# Mosfets.net
KiCad netlist of a schematic drawn in EAGLE
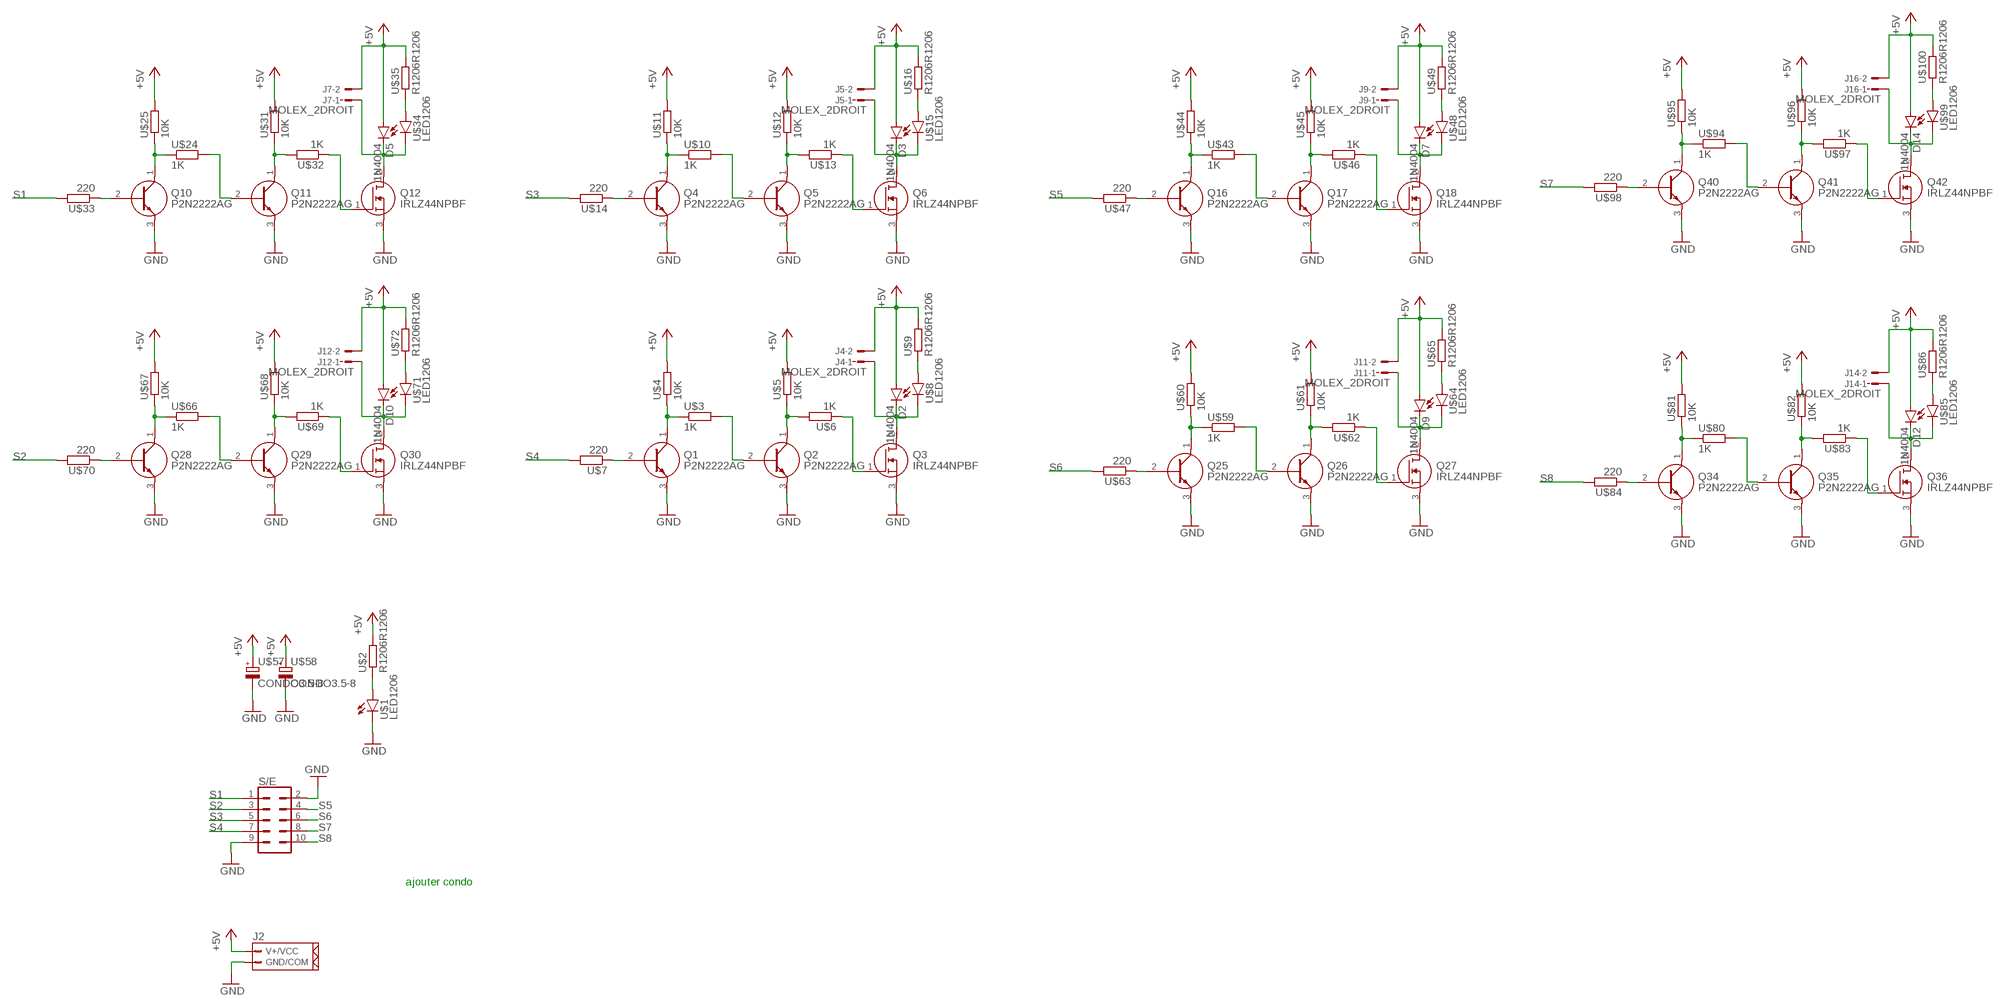
[diagram p0: schematic, sheet 1]

(export (version "E")
  (design (tool "Eeschema 10.0.6"))
  (components
    (comp (ref "D2")
      (value "1N4004")
      (footprint "eagle-import:DO41-10")
      (libsource (lib "eagle-import") (part "1N4004"))
    )
    (comp (ref "D3")
      (value "1N4004")
      (footprint "eagle-import:DO41-10")
      (libsource (lib "eagle-import") (part "1N4004"))
    )
    (comp (ref "D5")
      (value "1N4004")
      (footprint "eagle-import:DO41-10")
      (libsource (lib "eagle-import") (part "1N4004"))
    )
    (comp (ref "D7")
      (value "1N4004")
      (footprint "eagle-import:DO41-10")
      (libsource (lib "eagle-import") (part "1N4004"))
    )
    (comp (ref "D9")
      (value "1N4004")
      (footprint "eagle-import:DO41-10")
      (libsource (lib "eagle-import") (part "1N4004"))
    )
    (comp (ref "D10")
      (value "1N4004")
      (footprint "eagle-import:DO41-10")
      (libsource (lib "eagle-import") (part "1N4004"))
    )
    (comp (ref "D12")
      (value "1N4004")
      (footprint "eagle-import:DO41-10")
      (libsource (lib "eagle-import") (part "1N4004"))
    )
    (comp (ref "D14")
      (value "1N4004")
      (footprint "eagle-import:DO41-10")
      (libsource (lib "eagle-import") (part "1N4004"))
    )
    (comp (ref "J2")
      (value "MOLEX_2_PUISS90°")
      (footprint "eagle-import:CON_2_PUISS_90°")
      (libsource (lib "eagle-import") (part "MOLEX_2_PUISS90°"))
    )
    (comp (ref "J4")
      (value "MOLEX_2DROIT")
      (footprint "eagle-import:CON_2_DROIT")
      (fields (field (name "MF") "MOLEX"))
      (libsource (lib "eagle-import") (part "MOLEX_2DROIT"))
    )
    (comp (ref "J5")
      (value "MOLEX_2DROIT")
      (footprint "eagle-import:CON_2_DROIT")
      (fields (field (name "MF") "MOLEX"))
      (libsource (lib "eagle-import") (part "MOLEX_2DROIT"))
    )
    (comp (ref "J7")
      (value "MOLEX_2DROIT")
      (footprint "eagle-import:CON_2_DROIT")
      (fields (field (name "MF") "MOLEX"))
      (libsource (lib "eagle-import") (part "MOLEX_2DROIT"))
    )
    (comp (ref "J9")
      (value "MOLEX_2DROIT")
      (footprint "eagle-import:CON_2_DROIT")
      (fields (field (name "MF") "MOLEX"))
      (libsource (lib "eagle-import") (part "MOLEX_2DROIT"))
    )
    (comp (ref "J11")
      (value "MOLEX_2DROIT")
      (footprint "eagle-import:CON_2_DROIT")
      (fields (field (name "MF") "MOLEX"))
      (libsource (lib "eagle-import") (part "MOLEX_2DROIT"))
    )
    (comp (ref "J12")
      (value "MOLEX_2DROIT")
      (footprint "eagle-import:CON_2_DROIT")
      (fields (field (name "MF") "MOLEX"))
      (libsource (lib "eagle-import") (part "MOLEX_2DROIT"))
    )
    (comp (ref "J14")
      (value "MOLEX_2DROIT")
      (footprint "eagle-import:CON_2_DROIT")
      (fields (field (name "MF") "MOLEX"))
      (libsource (lib "eagle-import") (part "MOLEX_2DROIT"))
    )
    (comp (ref "J16")
      (value "MOLEX_2DROIT")
      (footprint "eagle-import:CON_2_DROIT")
      (fields (field (name "MF") "MOLEX"))
      (libsource (lib "eagle-import") (part "MOLEX_2DROIT"))
    )
    (comp (ref "Q1")
      (value "P2N2222AG")
      (footprint "eagle-import:TO-92")
      (fields (field (name "MOUSER_PART_NUMBER") "863-P2N2222AG") (field (name "RS_PART_NUMBER") "5449624P"))
      (libsource (lib "eagle-import") (part "P2N2222AG"))
    )
    (comp (ref "Q2")
      (value "P2N2222AG")
      (footprint "eagle-import:TO-92")
      (fields (field (name "MOUSER_PART_NUMBER") "863-P2N2222AG") (field (name "RS_PART_NUMBER") "5449624P"))
      (libsource (lib "eagle-import") (part "P2N2222AG"))
    )
    (comp (ref "Q3")
      (value "IRLZ44NPBF")
      (footprint "eagle-import:TO254P469X1042X1967-3P")
      (fields (field (name "RS_PART_NUMBER") "2509061408"))
      (libsource (lib "eagle-import") (part "IRLZ44NPBF"))
    )
    (comp (ref "Q4")
      (value "P2N2222AG")
      (footprint "eagle-import:TO-92")
      (fields (field (name "MOUSER_PART_NUMBER") "863-P2N2222AG") (field (name "RS_PART_NUMBER") "5449624P"))
      (libsource (lib "eagle-import") (part "P2N2222AG"))
    )
    (comp (ref "Q5")
      (value "P2N2222AG")
      (footprint "eagle-import:TO-92")
      (fields (field (name "MOUSER_PART_NUMBER") "863-P2N2222AG") (field (name "RS_PART_NUMBER") "5449624P"))
      (libsource (lib "eagle-import") (part "P2N2222AG"))
    )
    (comp (ref "Q6")
      (value "IRLZ44NPBF")
      (footprint "eagle-import:TO254P469X1042X1967-3P")
      (fields (field (name "RS_PART_NUMBER") "2509061408"))
      (libsource (lib "eagle-import") (part "IRLZ44NPBF"))
    )
    (comp (ref "Q10")
      (value "P2N2222AG")
      (footprint "eagle-import:TO-92")
      (fields (field (name "MOUSER_PART_NUMBER") "863-P2N2222AG") (field (name "RS_PART_NUMBER") "5449624P"))
      (libsource (lib "eagle-import") (part "P2N2222AG"))
    )
    (comp (ref "Q11")
      (value "P2N2222AG")
      (footprint "eagle-import:TO-92")
      (fields (field (name "MOUSER_PART_NUMBER") "863-P2N2222AG") (field (name "RS_PART_NUMBER") "5449624P"))
      (libsource (lib "eagle-import") (part "P2N2222AG"))
    )
    (comp (ref "Q12")
      (value "IRLZ44NPBF")
      (footprint "eagle-import:TO254P469X1042X1967-3P")
      (fields (field (name "RS_PART_NUMBER") "2509061408"))
      (libsource (lib "eagle-import") (part "IRLZ44NPBF"))
    )
    (comp (ref "Q16")
      (value "P2N2222AG")
      (footprint "eagle-import:TO-92")
      (fields (field (name "MOUSER_PART_NUMBER") "863-P2N2222AG") (field (name "RS_PART_NUMBER") "5449624P"))
      (libsource (lib "eagle-import") (part "P2N2222AG"))
    )
    (comp (ref "Q17")
      (value "P2N2222AG")
      (footprint "eagle-import:TO-92")
      (fields (field (name "MOUSER_PART_NUMBER") "863-P2N2222AG") (field (name "RS_PART_NUMBER") "5449624P"))
      (libsource (lib "eagle-import") (part "P2N2222AG"))
    )
    (comp (ref "Q18")
      (value "IRLZ44NPBF")
      (footprint "eagle-import:TO254P469X1042X1967-3P")
      (fields (field (name "RS_PART_NUMBER") "2509061408"))
      (libsource (lib "eagle-import") (part "IRLZ44NPBF"))
    )
    (comp (ref "Q25")
      (value "P2N2222AG")
      (footprint "eagle-import:TO-92")
      (fields (field (name "MOUSER_PART_NUMBER") "863-P2N2222AG") (field (name "RS_PART_NUMBER") "5449624P"))
      (libsource (lib "eagle-import") (part "P2N2222AG"))
    )
    (comp (ref "Q26")
      (value "P2N2222AG")
      (footprint "eagle-import:TO-92")
      (fields (field (name "MOUSER_PART_NUMBER") "863-P2N2222AG") (field (name "RS_PART_NUMBER") "5449624P"))
      (libsource (lib "eagle-import") (part "P2N2222AG"))
    )
    (comp (ref "Q27")
      (value "IRLZ44NPBF")
      (footprint "eagle-import:TO254P469X1042X1967-3P")
      (fields (field (name "RS_PART_NUMBER") "2509061408"))
      (libsource (lib "eagle-import") (part "IRLZ44NPBF"))
    )
    (comp (ref "Q28")
      (value "P2N2222AG")
      (footprint "eagle-import:TO-92")
      (fields (field (name "MOUSER_PART_NUMBER") "863-P2N2222AG") (field (name "RS_PART_NUMBER") "5449624P"))
      (libsource (lib "eagle-import") (part "P2N2222AG"))
    )
    (comp (ref "Q29")
      (value "P2N2222AG")
      (footprint "eagle-import:TO-92")
      (fields (field (name "MOUSER_PART_NUMBER") "863-P2N2222AG") (field (name "RS_PART_NUMBER") "5449624P"))
      (libsource (lib "eagle-import") (part "P2N2222AG"))
    )
    (comp (ref "Q30")
      (value "IRLZ44NPBF")
      (footprint "eagle-import:TO254P469X1042X1967-3P")
      (fields (field (name "RS_PART_NUMBER") "2509061408"))
      (libsource (lib "eagle-import") (part "IRLZ44NPBF"))
    )
    (comp (ref "Q34")
      (value "P2N2222AG")
      (footprint "eagle-import:TO-92")
      (fields (field (name "MOUSER_PART_NUMBER") "863-P2N2222AG") (field (name "RS_PART_NUMBER") "5449624P"))
      (libsource (lib "eagle-import") (part "P2N2222AG"))
    )
    (comp (ref "Q35")
      (value "P2N2222AG")
      (footprint "eagle-import:TO-92")
      (fields (field (name "MOUSER_PART_NUMBER") "863-P2N2222AG") (field (name "RS_PART_NUMBER") "5449624P"))
      (libsource (lib "eagle-import") (part "P2N2222AG"))
    )
    (comp (ref "Q36")
      (value "IRLZ44NPBF")
      (footprint "eagle-import:TO254P469X1042X1967-3P")
      (fields (field (name "RS_PART_NUMBER") "2509061408"))
      (libsource (lib "eagle-import") (part "IRLZ44NPBF"))
    )
    (comp (ref "Q40")
      (value "P2N2222AG")
      (footprint "eagle-import:TO-92")
      (fields (field (name "MOUSER_PART_NUMBER") "863-P2N2222AG") (field (name "RS_PART_NUMBER") "5449624P"))
      (libsource (lib "eagle-import") (part "P2N2222AG"))
    )
    (comp (ref "Q41")
      (value "P2N2222AG")
      (footprint "eagle-import:TO-92")
      (fields (field (name "MOUSER_PART_NUMBER") "863-P2N2222AG") (field (name "RS_PART_NUMBER") "5449624P"))
      (libsource (lib "eagle-import") (part "P2N2222AG"))
    )
    (comp (ref "Q42")
      (value "IRLZ44NPBF")
      (footprint "eagle-import:TO254P469X1042X1967-3P")
      (fields (field (name "RS_PART_NUMBER") "2509061408"))
      (libsource (lib "eagle-import") (part "IRLZ44NPBF"))
    )
    (comp (ref "S/E")
      (value "CON_5X2SHD")
      (footprint "eagle-import:2X5-SHROUDED")
      (libsource (lib "eagle-import") (part "CON_5X2SHD"))
    )
    (comp (ref "U$1")
      (value "LED1206")
      (footprint "eagle-import:1206")
      (libsource (lib "eagle-import") (part "LED1206"))
    )
    (comp (ref "U$2")
      (value "R1206R1206")
      (footprint "eagle-import:R1206")
      (libsource (lib "eagle-import") (part "R1206R1206"))
    )
    (comp (ref "U$3")
      (value "1K")
      (footprint "eagle-import:R1206")
      (libsource (lib "eagle-import") (part "R1206R1206"))
    )
    (comp (ref "U$4")
      (value "10K")
      (footprint "eagle-import:R1206")
      (libsource (lib "eagle-import") (part "R1206R1206"))
    )
    (comp (ref "U$5")
      (value "10K")
      (footprint "eagle-import:R1206")
      (libsource (lib "eagle-import") (part "R1206R1206"))
    )
    (comp (ref "U$6")
      (value "1K")
      (footprint "eagle-import:R1206")
      (libsource (lib "eagle-import") (part "R1206R1206"))
    )
    (comp (ref "U$7")
      (value "220")
      (footprint "eagle-import:R1206")
      (libsource (lib "eagle-import") (part "R1206R1206"))
    )
    (comp (ref "U$8")
      (value "LED1206")
      (footprint "eagle-import:1206")
      (libsource (lib "eagle-import") (part "LED1206"))
    )
    (comp (ref "U$9")
      (value "R1206R1206")
      (footprint "eagle-import:R1206")
      (libsource (lib "eagle-import") (part "R1206R1206"))
    )
    (comp (ref "U$10")
      (value "1K")
      (footprint "eagle-import:R1206")
      (libsource (lib "eagle-import") (part "R1206R1206"))
    )
    (comp (ref "U$11")
      (value "10K")
      (footprint "eagle-import:R1206")
      (libsource (lib "eagle-import") (part "R1206R1206"))
    )
    (comp (ref "U$12")
      (value "10K")
      (footprint "eagle-import:R1206")
      (libsource (lib "eagle-import") (part "R1206R1206"))
    )
    (comp (ref "U$13")
      (value "1K")
      (footprint "eagle-import:R1206")
      (libsource (lib "eagle-import") (part "R1206R1206"))
    )
    (comp (ref "U$14")
      (value "220")
      (footprint "eagle-import:R1206")
      (libsource (lib "eagle-import") (part "R1206R1206"))
    )
    (comp (ref "U$15")
      (value "LED1206")
      (footprint "eagle-import:1206")
      (libsource (lib "eagle-import") (part "LED1206"))
    )
    (comp (ref "U$16")
      (value "R1206R1206")
      (footprint "eagle-import:R1206")
      (libsource (lib "eagle-import") (part "R1206R1206"))
    )
    (comp (ref "U$24")
      (value "1K")
      (footprint "eagle-import:R1206")
      (libsource (lib "eagle-import") (part "R1206R1206"))
    )
    (comp (ref "U$25")
      (value "10K")
      (footprint "eagle-import:R1206")
      (libsource (lib "eagle-import") (part "R1206R1206"))
    )
    (comp (ref "U$31")
      (value "10K")
      (footprint "eagle-import:R1206")
      (libsource (lib "eagle-import") (part "R1206R1206"))
    )
    (comp (ref "U$32")
      (value "1K")
      (footprint "eagle-import:R1206")
      (libsource (lib "eagle-import") (part "R1206R1206"))
    )
    (comp (ref "U$33")
      (value "220")
      (footprint "eagle-import:R1206")
      (libsource (lib "eagle-import") (part "R1206R1206"))
    )
    (comp (ref "U$34")
      (value "LED1206")
      (footprint "eagle-import:1206")
      (libsource (lib "eagle-import") (part "LED1206"))
    )
    (comp (ref "U$35")
      (value "R1206R1206")
      (footprint "eagle-import:R1206")
      (libsource (lib "eagle-import") (part "R1206R1206"))
    )
    (comp (ref "U$43")
      (value "1K")
      (footprint "eagle-import:R1206")
      (libsource (lib "eagle-import") (part "R1206R1206"))
    )
    (comp (ref "U$44")
      (value "10K")
      (footprint "eagle-import:R1206")
      (libsource (lib "eagle-import") (part "R1206R1206"))
    )
    (comp (ref "U$45")
      (value "10K")
      (footprint "eagle-import:R1206")
      (libsource (lib "eagle-import") (part "R1206R1206"))
    )
    (comp (ref "U$46")
      (value "1K")
      (footprint "eagle-import:R1206")
      (libsource (lib "eagle-import") (part "R1206R1206"))
    )
    (comp (ref "U$47")
      (value "220")
      (footprint "eagle-import:R1206")
      (libsource (lib "eagle-import") (part "R1206R1206"))
    )
    (comp (ref "U$48")
      (value "LED1206")
      (footprint "eagle-import:1206")
      (libsource (lib "eagle-import") (part "LED1206"))
    )
    (comp (ref "U$49")
      (value "R1206R1206")
      (footprint "eagle-import:R1206")
      (libsource (lib "eagle-import") (part "R1206R1206"))
    )
    (comp (ref "U$57")
      (value "CONDO3.5-8")
      (footprint "eagle-import:E3,5-8")
      (libsource (lib "eagle-import") (part "CONDO3.5-8"))
    )
    (comp (ref "U$58")
      (value "CONDO3.5-8")
      (footprint "eagle-import:E3,5-8")
      (libsource (lib "eagle-import") (part "CONDO3.5-8"))
    )
    (comp (ref "U$59")
      (value "1K")
      (footprint "eagle-import:R1206")
      (libsource (lib "eagle-import") (part "R1206R1206"))
    )
    (comp (ref "U$60")
      (value "10K")
      (footprint "eagle-import:R1206")
      (libsource (lib "eagle-import") (part "R1206R1206"))
    )
    (comp (ref "U$61")
      (value "10K")
      (footprint "eagle-import:R1206")
      (libsource (lib "eagle-import") (part "R1206R1206"))
    )
    (comp (ref "U$62")
      (value "1K")
      (footprint "eagle-import:R1206")
      (libsource (lib "eagle-import") (part "R1206R1206"))
    )
    (comp (ref "U$63")
      (value "220")
      (footprint "eagle-import:R1206")
      (libsource (lib "eagle-import") (part "R1206R1206"))
    )
    (comp (ref "U$64")
      (value "LED1206")
      (footprint "eagle-import:1206")
      (libsource (lib "eagle-import") (part "LED1206"))
    )
    (comp (ref "U$65")
      (value "R1206R1206")
      (footprint "eagle-import:R1206")
      (libsource (lib "eagle-import") (part "R1206R1206"))
    )
    (comp (ref "U$66")
      (value "1K")
      (footprint "eagle-import:R1206")
      (libsource (lib "eagle-import") (part "R1206R1206"))
    )
    (comp (ref "U$67")
      (value "10K")
      (footprint "eagle-import:R1206")
      (libsource (lib "eagle-import") (part "R1206R1206"))
    )
    (comp (ref "U$68")
      (value "10K")
      (footprint "eagle-import:R1206")
      (libsource (lib "eagle-import") (part "R1206R1206"))
    )
    (comp (ref "U$69")
      (value "1K")
      (footprint "eagle-import:R1206")
      (libsource (lib "eagle-import") (part "R1206R1206"))
    )
    (comp (ref "U$70")
      (value "220")
      (footprint "eagle-import:R1206")
      (libsource (lib "eagle-import") (part "R1206R1206"))
    )
    (comp (ref "U$71")
      (value "LED1206")
      (footprint "eagle-import:1206")
      (libsource (lib "eagle-import") (part "LED1206"))
    )
    (comp (ref "U$72")
      (value "R1206R1206")
      (footprint "eagle-import:R1206")
      (libsource (lib "eagle-import") (part "R1206R1206"))
    )
    (comp (ref "U$80")
      (value "1K")
      (footprint "eagle-import:R1206")
      (libsource (lib "eagle-import") (part "R1206R1206"))
    )
    (comp (ref "U$81")
      (value "10K")
      (footprint "eagle-import:R1206")
      (libsource (lib "eagle-import") (part "R1206R1206"))
    )
    (comp (ref "U$82")
      (value "10K")
      (footprint "eagle-import:R1206")
      (libsource (lib "eagle-import") (part "R1206R1206"))
    )
    (comp (ref "U$83")
      (value "1K")
      (footprint "eagle-import:R1206")
      (libsource (lib "eagle-import") (part "R1206R1206"))
    )
    (comp (ref "U$84")
      (value "220")
      (footprint "eagle-import:R1206")
      (libsource (lib "eagle-import") (part "R1206R1206"))
    )
    (comp (ref "U$85")
      (value "LED1206")
      (footprint "eagle-import:1206")
      (libsource (lib "eagle-import") (part "LED1206"))
    )
    (comp (ref "U$86")
      (value "R1206R1206")
      (footprint "eagle-import:R1206")
      (libsource (lib "eagle-import") (part "R1206R1206"))
    )
    (comp (ref "U$94")
      (value "1K")
      (footprint "eagle-import:R1206")
      (libsource (lib "eagle-import") (part "R1206R1206"))
    )
    (comp (ref "U$95")
      (value "10K")
      (footprint "eagle-import:R1206")
      (libsource (lib "eagle-import") (part "R1206R1206"))
    )
    (comp (ref "U$96")
      (value "10K")
      (footprint "eagle-import:R1206")
      (libsource (lib "eagle-import") (part "R1206R1206"))
    )
    (comp (ref "U$97")
      (value "1K")
      (footprint "eagle-import:R1206")
      (libsource (lib "eagle-import") (part "R1206R1206"))
    )
    (comp (ref "U$98")
      (value "220")
      (footprint "eagle-import:R1206")
      (libsource (lib "eagle-import") (part "R1206R1206"))
    )
    (comp (ref "U$99")
      (value "LED1206")
      (footprint "eagle-import:1206")
      (libsource (lib "eagle-import") (part "LED1206"))
    )
    (comp (ref "U$100")
      (value "R1206R1206")
      (footprint "eagle-import:R1206")
      (libsource (lib "eagle-import") (part "R1206R1206"))
    )
  )
  (nets
    (net (code "1") (name "+5V") (class "Default")
      (node (ref "D10") (pin "A") (pinfunction "A_A") (pintype "passive"))
      (node (ref "D12") (pin "A") (pinfunction "A_A") (pintype "passive"))
      (node (ref "D14") (pin "A") (pinfunction "A_A") (pintype "passive"))
      (node (ref "D2") (pin "A") (pinfunction "A_A") (pintype "passive"))
      (node (ref "D3") (pin "A") (pinfunction "A_A") (pintype "passive"))
      (node (ref "D5") (pin "A") (pinfunction "A_A") (pintype "passive"))
      (node (ref "D7") (pin "A") (pinfunction "A_A") (pintype "passive"))
      (node (ref "D9") (pin "A") (pinfunction "A_A") (pintype "passive"))
      (node (ref "J11") (pin "2") (pinfunction "S_2") (pintype "passive"))
      (node (ref "J12") (pin "2") (pinfunction "S_2") (pintype "passive"))
      (node (ref "J14") (pin "2") (pinfunction "S_2") (pintype "passive"))
      (node (ref "J16") (pin "2") (pinfunction "S_2") (pintype "passive"))
      (node (ref "J2") (pin "P$2") (pinfunction "V+/VCC_P$2") (pintype "passive"))
      (node (ref "J4") (pin "2") (pinfunction "S_2") (pintype "passive"))
      (node (ref "J5") (pin "2") (pinfunction "S_2") (pintype "passive"))
      (node (ref "J7") (pin "2") (pinfunction "S_2") (pintype "passive"))
      (node (ref "J9") (pin "2") (pinfunction "S_2") (pintype "passive"))
      (node (ref "U$100") (pin "2") (pinfunction "2_2") (pintype "passive"))
      (node (ref "U$11") (pin "2") (pinfunction "2_2") (pintype "passive"))
      (node (ref "U$12") (pin "2") (pinfunction "2_2") (pintype "passive"))
      (node (ref "U$16") (pin "2") (pinfunction "2_2") (pintype "passive"))
      (node (ref "U$2") (pin "2") (pinfunction "2_2") (pintype "passive"))
      (node (ref "U$25") (pin "2") (pinfunction "2_2") (pintype "passive"))
      (node (ref "U$31") (pin "2") (pinfunction "2_2") (pintype "passive"))
      (node (ref "U$35") (pin "2") (pinfunction "2_2") (pintype "passive"))
      (node (ref "U$4") (pin "2") (pinfunction "2_2") (pintype "passive"))
      (node (ref "U$44") (pin "2") (pinfunction "2_2") (pintype "passive"))
      (node (ref "U$45") (pin "2") (pinfunction "2_2") (pintype "passive"))
      (node (ref "U$49") (pin "2") (pinfunction "2_2") (pintype "passive"))
      (node (ref "U$5") (pin "2") (pinfunction "2_2") (pintype "passive"))
      (node (ref "U$57") (pin "+") (pinfunction "+_+") (pintype "passive"))
      (node (ref "U$58") (pin "+") (pinfunction "+_+") (pintype "passive"))
      (node (ref "U$60") (pin "2") (pinfunction "2_2") (pintype "passive"))
      (node (ref "U$61") (pin "2") (pinfunction "2_2") (pintype "passive"))
      (node (ref "U$65") (pin "2") (pinfunction "2_2") (pintype "passive"))
      (node (ref "U$67") (pin "2") (pinfunction "2_2") (pintype "passive"))
      (node (ref "U$68") (pin "2") (pinfunction "2_2") (pintype "passive"))
      (node (ref "U$72") (pin "2") (pinfunction "2_2") (pintype "passive"))
      (node (ref "U$81") (pin "2") (pinfunction "2_2") (pintype "passive"))
      (node (ref "U$82") (pin "2") (pinfunction "2_2") (pintype "passive"))
      (node (ref "U$86") (pin "2") (pinfunction "2_2") (pintype "passive"))
      (node (ref "U$9") (pin "2") (pinfunction "2_2") (pintype "passive"))
      (node (ref "U$95") (pin "2") (pinfunction "2_2") (pintype "passive"))
      (node (ref "U$96") (pin "2") (pinfunction "2_2") (pintype "passive"))
    )
    (net (code "2") (name "/S1") (class "Default")
      (node (ref "S/E") (pin "1") (pinfunction "1_1") (pintype "passive"))
      (node (ref "U$33") (pin "2") (pinfunction "2_2") (pintype "passive"))
    )
    (net (code "3") (name "/S2") (class "Default")
      (node (ref "S/E") (pin "3") (pinfunction "3_3") (pintype "passive"))
      (node (ref "U$70") (pin "2") (pinfunction "2_2") (pintype "passive"))
    )
    (net (code "4") (name "/S3") (class "Default")
      (node (ref "S/E") (pin "5") (pinfunction "5_5") (pintype "passive"))
      (node (ref "U$14") (pin "2") (pinfunction "2_2") (pintype "passive"))
    )
    (net (code "5") (name "/S4") (class "Default")
      (node (ref "S/E") (pin "7") (pinfunction "7_7") (pintype "passive"))
      (node (ref "U$7") (pin "2") (pinfunction "2_2") (pintype "passive"))
    )
    (net (code "6") (name "/S5") (class "Default")
      (node (ref "S/E") (pin "4") (pinfunction "4_4") (pintype "passive"))
      (node (ref "U$47") (pin "2") (pinfunction "2_2") (pintype "passive"))
    )
    (net (code "7") (name "/S6") (class "Default")
      (node (ref "S/E") (pin "6") (pinfunction "6_6") (pintype "passive"))
      (node (ref "U$63") (pin "2") (pinfunction "2_2") (pintype "passive"))
    )
    (net (code "8") (name "/S7") (class "Default")
      (node (ref "S/E") (pin "8") (pinfunction "8_8") (pintype "passive"))
      (node (ref "U$98") (pin "2") (pinfunction "2_2") (pintype "passive"))
    )
    (net (code "9") (name "/S8") (class "Default")
      (node (ref "S/E") (pin "10") (pinfunction "10_10") (pintype "passive"))
      (node (ref "U$84") (pin "2") (pinfunction "2_2") (pintype "passive"))
    )
    (net (code "10") (name "GND") (class "Default")
      (node (ref "J2") (pin "P$1") (pinfunction "GND/COM_P$1") (pintype "passive"))
      (node (ref "Q1") (pin "3") (pinfunction "E_3") (pintype "bidirectional"))
      (node (ref "Q10") (pin "3") (pinfunction "E_3") (pintype "bidirectional"))
      (node (ref "Q11") (pin "3") (pinfunction "E_3") (pintype "bidirectional"))
      (node (ref "Q12") (pin "3") (pinfunction "S_3") (pintype "input"))
      (node (ref "Q16") (pin "3") (pinfunction "E_3") (pintype "bidirectional"))
      (node (ref "Q17") (pin "3") (pinfunction "E_3") (pintype "bidirectional"))
      (node (ref "Q18") (pin "3") (pinfunction "S_3") (pintype "input"))
      (node (ref "Q2") (pin "3") (pinfunction "E_3") (pintype "bidirectional"))
      (node (ref "Q25") (pin "3") (pinfunction "E_3") (pintype "bidirectional"))
      (node (ref "Q26") (pin "3") (pinfunction "E_3") (pintype "bidirectional"))
      (node (ref "Q27") (pin "3") (pinfunction "S_3") (pintype "input"))
      (node (ref "Q28") (pin "3") (pinfunction "E_3") (pintype "bidirectional"))
      (node (ref "Q29") (pin "3") (pinfunction "E_3") (pintype "bidirectional"))
      (node (ref "Q3") (pin "3") (pinfunction "S_3") (pintype "input"))
      (node (ref "Q30") (pin "3") (pinfunction "S_3") (pintype "input"))
      (node (ref "Q34") (pin "3") (pinfunction "E_3") (pintype "bidirectional"))
      (node (ref "Q35") (pin "3") (pinfunction "E_3") (pintype "bidirectional"))
      (node (ref "Q36") (pin "3") (pinfunction "S_3") (pintype "input"))
      (node (ref "Q4") (pin "3") (pinfunction "E_3") (pintype "bidirectional"))
      (node (ref "Q40") (pin "3") (pinfunction "E_3") (pintype "bidirectional"))
      (node (ref "Q41") (pin "3") (pinfunction "E_3") (pintype "bidirectional"))
      (node (ref "Q42") (pin "3") (pinfunction "S_3") (pintype "input"))
      (node (ref "Q5") (pin "3") (pinfunction "E_3") (pintype "bidirectional"))
      (node (ref "Q6") (pin "3") (pinfunction "S_3") (pintype "input"))
      (node (ref "S/E") (pin "2") (pinfunction "2_2") (pintype "passive"))
      (node (ref "S/E") (pin "9") (pinfunction "9_9") (pintype "passive"))
      (node (ref "U$1") (pin "C") (pinfunction "C_C") (pintype "passive"))
      (node (ref "U$57") (pin "-") (pinfunction "-_-") (pintype "passive"))
      (node (ref "U$58") (pin "-") (pinfunction "-_-") (pintype "passive"))
    )
    (net (code "11") (name "Net-(J4A-S)") (class "Default")
      (node (ref "D2") (pin "C") (pinfunction "C_C") (pintype "passive"))
      (node (ref "J4") (pin "1") (pinfunction "S_1") (pintype "passive"))
      (node (ref "Q3") (pin "2") (pinfunction "D_2") (pintype "output"))
      (node (ref "U$8") (pin "C") (pinfunction "C_C") (pintype "passive"))
    )
    (net (code "12") (name "Net-(J5A-S)") (class "Default")
      (node (ref "D3") (pin "C") (pinfunction "C_C") (pintype "passive"))
      (node (ref "J5") (pin "1") (pinfunction "S_1") (pintype "passive"))
      (node (ref "Q6") (pin "2") (pinfunction "D_2") (pintype "output"))
      (node (ref "U$15") (pin "C") (pinfunction "C_C") (pintype "passive"))
    )
    (net (code "13") (name "Net-(J7A-S)") (class "Default")
      (node (ref "D5") (pin "C") (pinfunction "C_C") (pintype "passive"))
      (node (ref "J7") (pin "1") (pinfunction "S_1") (pintype "passive"))
      (node (ref "Q12") (pin "2") (pinfunction "D_2") (pintype "output"))
      (node (ref "U$34") (pin "C") (pinfunction "C_C") (pintype "passive"))
    )
    (net (code "14") (name "Net-(J9A-S)") (class "Default")
      (node (ref "D7") (pin "C") (pinfunction "C_C") (pintype "passive"))
      (node (ref "J9") (pin "1") (pinfunction "S_1") (pintype "passive"))
      (node (ref "Q18") (pin "2") (pinfunction "D_2") (pintype "output"))
      (node (ref "U$48") (pin "C") (pinfunction "C_C") (pintype "passive"))
    )
    (net (code "15") (name "Net-(J11A-S)") (class "Default")
      (node (ref "D9") (pin "C") (pinfunction "C_C") (pintype "passive"))
      (node (ref "J11") (pin "1") (pinfunction "S_1") (pintype "passive"))
      (node (ref "Q27") (pin "2") (pinfunction "D_2") (pintype "output"))
      (node (ref "U$64") (pin "C") (pinfunction "C_C") (pintype "passive"))
    )
    (net (code "16") (name "Net-(J12A-S)") (class "Default")
      (node (ref "D10") (pin "C") (pinfunction "C_C") (pintype "passive"))
      (node (ref "J12") (pin "1") (pinfunction "S_1") (pintype "passive"))
      (node (ref "Q30") (pin "2") (pinfunction "D_2") (pintype "output"))
      (node (ref "U$71") (pin "C") (pinfunction "C_C") (pintype "passive"))
    )
    (net (code "17") (name "Net-(J14A-S)") (class "Default")
      (node (ref "D12") (pin "C") (pinfunction "C_C") (pintype "passive"))
      (node (ref "J14") (pin "1") (pinfunction "S_1") (pintype "passive"))
      (node (ref "Q36") (pin "2") (pinfunction "D_2") (pintype "output"))
      (node (ref "U$85") (pin "C") (pinfunction "C_C") (pintype "passive"))
    )
    (net (code "18") (name "Net-(J16A-S)") (class "Default")
      (node (ref "D14") (pin "C") (pinfunction "C_C") (pintype "passive"))
      (node (ref "J16") (pin "1") (pinfunction "S_1") (pintype "passive"))
      (node (ref "Q42") (pin "2") (pinfunction "D_2") (pintype "output"))
      (node (ref "U$99") (pin "C") (pinfunction "C_C") (pintype "passive"))
    )
    (net (code "19") (name "Net-(Q1-B)") (class "Default")
      (node (ref "Q1") (pin "2") (pinfunction "B_2") (pintype "bidirectional"))
      (node (ref "U$7") (pin "1") (pinfunction "1_1") (pintype "passive"))
    )
    (net (code "20") (name "Net-(Q1-C)") (class "Default")
      (node (ref "Q1") (pin "1") (pinfunction "C_1") (pintype "bidirectional"))
      (node (ref "U$3") (pin "1") (pinfunction "1_1") (pintype "passive"))
      (node (ref "U$4") (pin "1") (pinfunction "1_1") (pintype "passive"))
    )
    (net (code "21") (name "Net-(Q2-B)") (class "Default")
      (node (ref "Q2") (pin "2") (pinfunction "B_2") (pintype "bidirectional"))
      (node (ref "U$3") (pin "2") (pinfunction "2_2") (pintype "passive"))
    )
    (net (code "22") (name "Net-(Q2-C)") (class "Default")
      (node (ref "Q2") (pin "1") (pinfunction "C_1") (pintype "bidirectional"))
      (node (ref "U$5") (pin "1") (pinfunction "1_1") (pintype "passive"))
      (node (ref "U$6") (pin "2") (pinfunction "2_2") (pintype "passive"))
    )
    (net (code "23") (name "Net-(Q3-G)") (class "Default")
      (node (ref "Q3") (pin "1") (pinfunction "G_1") (pintype "input"))
      (node (ref "U$6") (pin "1") (pinfunction "1_1") (pintype "passive"))
    )
    (net (code "24") (name "Net-(Q4-B)") (class "Default")
      (node (ref "Q4") (pin "2") (pinfunction "B_2") (pintype "bidirectional"))
      (node (ref "U$14") (pin "1") (pinfunction "1_1") (pintype "passive"))
    )
    (net (code "25") (name "Net-(Q4-C)") (class "Default")
      (node (ref "Q4") (pin "1") (pinfunction "C_1") (pintype "bidirectional"))
      (node (ref "U$10") (pin "1") (pinfunction "1_1") (pintype "passive"))
      (node (ref "U$11") (pin "1") (pinfunction "1_1") (pintype "passive"))
    )
    (net (code "26") (name "Net-(Q5-B)") (class "Default")
      (node (ref "Q5") (pin "2") (pinfunction "B_2") (pintype "bidirectional"))
      (node (ref "U$10") (pin "2") (pinfunction "2_2") (pintype "passive"))
    )
    (net (code "27") (name "Net-(Q5-C)") (class "Default")
      (node (ref "Q5") (pin "1") (pinfunction "C_1") (pintype "bidirectional"))
      (node (ref "U$12") (pin "1") (pinfunction "1_1") (pintype "passive"))
      (node (ref "U$13") (pin "2") (pinfunction "2_2") (pintype "passive"))
    )
    (net (code "28") (name "Net-(Q6-G)") (class "Default")
      (node (ref "Q6") (pin "1") (pinfunction "G_1") (pintype "input"))
      (node (ref "U$13") (pin "1") (pinfunction "1_1") (pintype "passive"))
    )
    (net (code "29") (name "Net-(Q10-B)") (class "Default")
      (node (ref "Q10") (pin "2") (pinfunction "B_2") (pintype "bidirectional"))
      (node (ref "U$33") (pin "1") (pinfunction "1_1") (pintype "passive"))
    )
    (net (code "30") (name "Net-(Q10-C)") (class "Default")
      (node (ref "Q10") (pin "1") (pinfunction "C_1") (pintype "bidirectional"))
      (node (ref "U$24") (pin "1") (pinfunction "1_1") (pintype "passive"))
      (node (ref "U$25") (pin "1") (pinfunction "1_1") (pintype "passive"))
    )
    (net (code "31") (name "Net-(Q11-B)") (class "Default")
      (node (ref "Q11") (pin "2") (pinfunction "B_2") (pintype "bidirectional"))
      (node (ref "U$24") (pin "2") (pinfunction "2_2") (pintype "passive"))
    )
    (net (code "32") (name "Net-(Q11-C)") (class "Default")
      (node (ref "Q11") (pin "1") (pinfunction "C_1") (pintype "bidirectional"))
      (node (ref "U$31") (pin "1") (pinfunction "1_1") (pintype "passive"))
      (node (ref "U$32") (pin "2") (pinfunction "2_2") (pintype "passive"))
    )
    (net (code "33") (name "Net-(Q12-G)") (class "Default")
      (node (ref "Q12") (pin "1") (pinfunction "G_1") (pintype "input"))
      (node (ref "U$32") (pin "1") (pinfunction "1_1") (pintype "passive"))
    )
    (net (code "34") (name "Net-(Q16-B)") (class "Default")
      (node (ref "Q16") (pin "2") (pinfunction "B_2") (pintype "bidirectional"))
      (node (ref "U$47") (pin "1") (pinfunction "1_1") (pintype "passive"))
    )
    (net (code "35") (name "Net-(Q16-C)") (class "Default")
      (node (ref "Q16") (pin "1") (pinfunction "C_1") (pintype "bidirectional"))
      (node (ref "U$43") (pin "1") (pinfunction "1_1") (pintype "passive"))
      (node (ref "U$44") (pin "1") (pinfunction "1_1") (pintype "passive"))
    )
    (net (code "36") (name "Net-(Q17-B)") (class "Default")
      (node (ref "Q17") (pin "2") (pinfunction "B_2") (pintype "bidirectional"))
      (node (ref "U$43") (pin "2") (pinfunction "2_2") (pintype "passive"))
    )
    (net (code "37") (name "Net-(Q17-C)") (class "Default")
      (node (ref "Q17") (pin "1") (pinfunction "C_1") (pintype "bidirectional"))
      (node (ref "U$45") (pin "1") (pinfunction "1_1") (pintype "passive"))
      (node (ref "U$46") (pin "2") (pinfunction "2_2") (pintype "passive"))
    )
    (net (code "38") (name "Net-(Q18-G)") (class "Default")
      (node (ref "Q18") (pin "1") (pinfunction "G_1") (pintype "input"))
      (node (ref "U$46") (pin "1") (pinfunction "1_1") (pintype "passive"))
    )
    (net (code "39") (name "Net-(Q25-B)") (class "Default")
      (node (ref "Q25") (pin "2") (pinfunction "B_2") (pintype "bidirectional"))
      (node (ref "U$63") (pin "1") (pinfunction "1_1") (pintype "passive"))
    )
    (net (code "40") (name "Net-(Q25-C)") (class "Default")
      (node (ref "Q25") (pin "1") (pinfunction "C_1") (pintype "bidirectional"))
      (node (ref "U$59") (pin "1") (pinfunction "1_1") (pintype "passive"))
      (node (ref "U$60") (pin "1") (pinfunction "1_1") (pintype "passive"))
    )
    (net (code "41") (name "Net-(Q26-B)") (class "Default")
      (node (ref "Q26") (pin "2") (pinfunction "B_2") (pintype "bidirectional"))
      (node (ref "U$59") (pin "2") (pinfunction "2_2") (pintype "passive"))
    )
    (net (code "42") (name "Net-(Q26-C)") (class "Default")
      (node (ref "Q26") (pin "1") (pinfunction "C_1") (pintype "bidirectional"))
      (node (ref "U$61") (pin "1") (pinfunction "1_1") (pintype "passive"))
      (node (ref "U$62") (pin "2") (pinfunction "2_2") (pintype "passive"))
    )
    (net (code "43") (name "Net-(Q27-G)") (class "Default")
      (node (ref "Q27") (pin "1") (pinfunction "G_1") (pintype "input"))
      (node (ref "U$62") (pin "1") (pinfunction "1_1") (pintype "passive"))
    )
    (net (code "44") (name "Net-(Q28-B)") (class "Default")
      (node (ref "Q28") (pin "2") (pinfunction "B_2") (pintype "bidirectional"))
      (node (ref "U$70") (pin "1") (pinfunction "1_1") (pintype "passive"))
    )
    (net (code "45") (name "Net-(Q28-C)") (class "Default")
      (node (ref "Q28") (pin "1") (pinfunction "C_1") (pintype "bidirectional"))
      (node (ref "U$66") (pin "1") (pinfunction "1_1") (pintype "passive"))
      (node (ref "U$67") (pin "1") (pinfunction "1_1") (pintype "passive"))
    )
    (net (code "46") (name "Net-(Q29-B)") (class "Default")
      (node (ref "Q29") (pin "2") (pinfunction "B_2") (pintype "bidirectional"))
      (node (ref "U$66") (pin "2") (pinfunction "2_2") (pintype "passive"))
    )
    (net (code "47") (name "Net-(Q29-C)") (class "Default")
      (node (ref "Q29") (pin "1") (pinfunction "C_1") (pintype "bidirectional"))
      (node (ref "U$68") (pin "1") (pinfunction "1_1") (pintype "passive"))
      (node (ref "U$69") (pin "2") (pinfunction "2_2") (pintype "passive"))
    )
    (net (code "48") (name "Net-(Q30-G)") (class "Default")
      (node (ref "Q30") (pin "1") (pinfunction "G_1") (pintype "input"))
      (node (ref "U$69") (pin "1") (pinfunction "1_1") (pintype "passive"))
    )
    (net (code "49") (name "Net-(Q34-B)") (class "Default")
      (node (ref "Q34") (pin "2") (pinfunction "B_2") (pintype "bidirectional"))
      (node (ref "U$84") (pin "1") (pinfunction "1_1") (pintype "passive"))
    )
    (net (code "50") (name "Net-(Q34-C)") (class "Default")
      (node (ref "Q34") (pin "1") (pinfunction "C_1") (pintype "bidirectional"))
      (node (ref "U$80") (pin "1") (pinfunction "1_1") (pintype "passive"))
      (node (ref "U$81") (pin "1") (pinfunction "1_1") (pintype "passive"))
    )
    (net (code "51") (name "Net-(Q35-B)") (class "Default")
      (node (ref "Q35") (pin "2") (pinfunction "B_2") (pintype "bidirectional"))
      (node (ref "U$80") (pin "2") (pinfunction "2_2") (pintype "passive"))
    )
    (net (code "52") (name "Net-(Q35-C)") (class "Default")
      (node (ref "Q35") (pin "1") (pinfunction "C_1") (pintype "bidirectional"))
      (node (ref "U$82") (pin "1") (pinfunction "1_1") (pintype "passive"))
      (node (ref "U$83") (pin "2") (pinfunction "2_2") (pintype "passive"))
    )
    (net (code "53") (name "Net-(Q36-G)") (class "Default")
      (node (ref "Q36") (pin "1") (pinfunction "G_1") (pintype "input"))
      (node (ref "U$83") (pin "1") (pinfunction "1_1") (pintype "passive"))
    )
    (net (code "54") (name "Net-(Q40-B)") (class "Default")
      (node (ref "Q40") (pin "2") (pinfunction "B_2") (pintype "bidirectional"))
      (node (ref "U$98") (pin "1") (pinfunction "1_1") (pintype "passive"))
    )
    (net (code "55") (name "Net-(Q40-C)") (class "Default")
      (node (ref "Q40") (pin "1") (pinfunction "C_1") (pintype "bidirectional"))
      (node (ref "U$94") (pin "1") (pinfunction "1_1") (pintype "passive"))
      (node (ref "U$95") (pin "1") (pinfunction "1_1") (pintype "passive"))
    )
    (net (code "56") (name "Net-(Q41-B)") (class "Default")
      (node (ref "Q41") (pin "2") (pinfunction "B_2") (pintype "bidirectional"))
      (node (ref "U$94") (pin "2") (pinfunction "2_2") (pintype "passive"))
    )
    (net (code "57") (name "Net-(Q41-C)") (class "Default")
      (node (ref "Q41") (pin "1") (pinfunction "C_1") (pintype "bidirectional"))
      (node (ref "U$96") (pin "1") (pinfunction "1_1") (pintype "passive"))
      (node (ref "U$97") (pin "2") (pinfunction "2_2") (pintype "passive"))
    )
    (net (code "58") (name "Net-(Q42-G)") (class "Default")
      (node (ref "Q42") (pin "1") (pinfunction "G_1") (pintype "input"))
      (node (ref "U$97") (pin "1") (pinfunction "1_1") (pintype "passive"))
    )
    (net (code "59") (name "Net-(U$1-PadA)") (class "Default")
      (node (ref "U$1") (pin "A") (pinfunction "A_A") (pintype "passive"))
      (node (ref "U$2") (pin "1") (pinfunction "1_1") (pintype "passive"))
    )
    (net (code "60") (name "Net-(U$8-PadA)") (class "Default")
      (node (ref "U$8") (pin "A") (pinfunction "A_A") (pintype "passive"))
      (node (ref "U$9") (pin "1") (pinfunction "1_1") (pintype "passive"))
    )
    (net (code "61") (name "Net-(U$15-PadA)") (class "Default")
      (node (ref "U$15") (pin "A") (pinfunction "A_A") (pintype "passive"))
      (node (ref "U$16") (pin "1") (pinfunction "1_1") (pintype "passive"))
    )
    (net (code "62") (name "Net-(U$34-PadA)") (class "Default")
      (node (ref "U$34") (pin "A") (pinfunction "A_A") (pintype "passive"))
      (node (ref "U$35") (pin "1") (pinfunction "1_1") (pintype "passive"))
    )
    (net (code "63") (name "Net-(U$48-PadA)") (class "Default")
      (node (ref "U$48") (pin "A") (pinfunction "A_A") (pintype "passive"))
      (node (ref "U$49") (pin "1") (pinfunction "1_1") (pintype "passive"))
    )
    (net (code "64") (name "Net-(U$64-PadA)") (class "Default")
      (node (ref "U$64") (pin "A") (pinfunction "A_A") (pintype "passive"))
      (node (ref "U$65") (pin "1") (pinfunction "1_1") (pintype "passive"))
    )
    (net (code "65") (name "Net-(U$71-PadA)") (class "Default")
      (node (ref "U$71") (pin "A") (pinfunction "A_A") (pintype "passive"))
      (node (ref "U$72") (pin "1") (pinfunction "1_1") (pintype "passive"))
    )
    (net (code "66") (name "Net-(U$85-PadA)") (class "Default")
      (node (ref "U$85") (pin "A") (pinfunction "A_A") (pintype "passive"))
      (node (ref "U$86") (pin "1") (pinfunction "1_1") (pintype "passive"))
    )
    (net (code "67") (name "Net-(U$100-Pad1)") (class "Default")
      (node (ref "U$100") (pin "1") (pinfunction "1_1") (pintype "passive"))
      (node (ref "U$99") (pin "A") (pinfunction "A_A") (pintype "passive"))
    )
  )
)
